# Schematic.net
KiCad netlist of a schematic drawn in Altium Designer
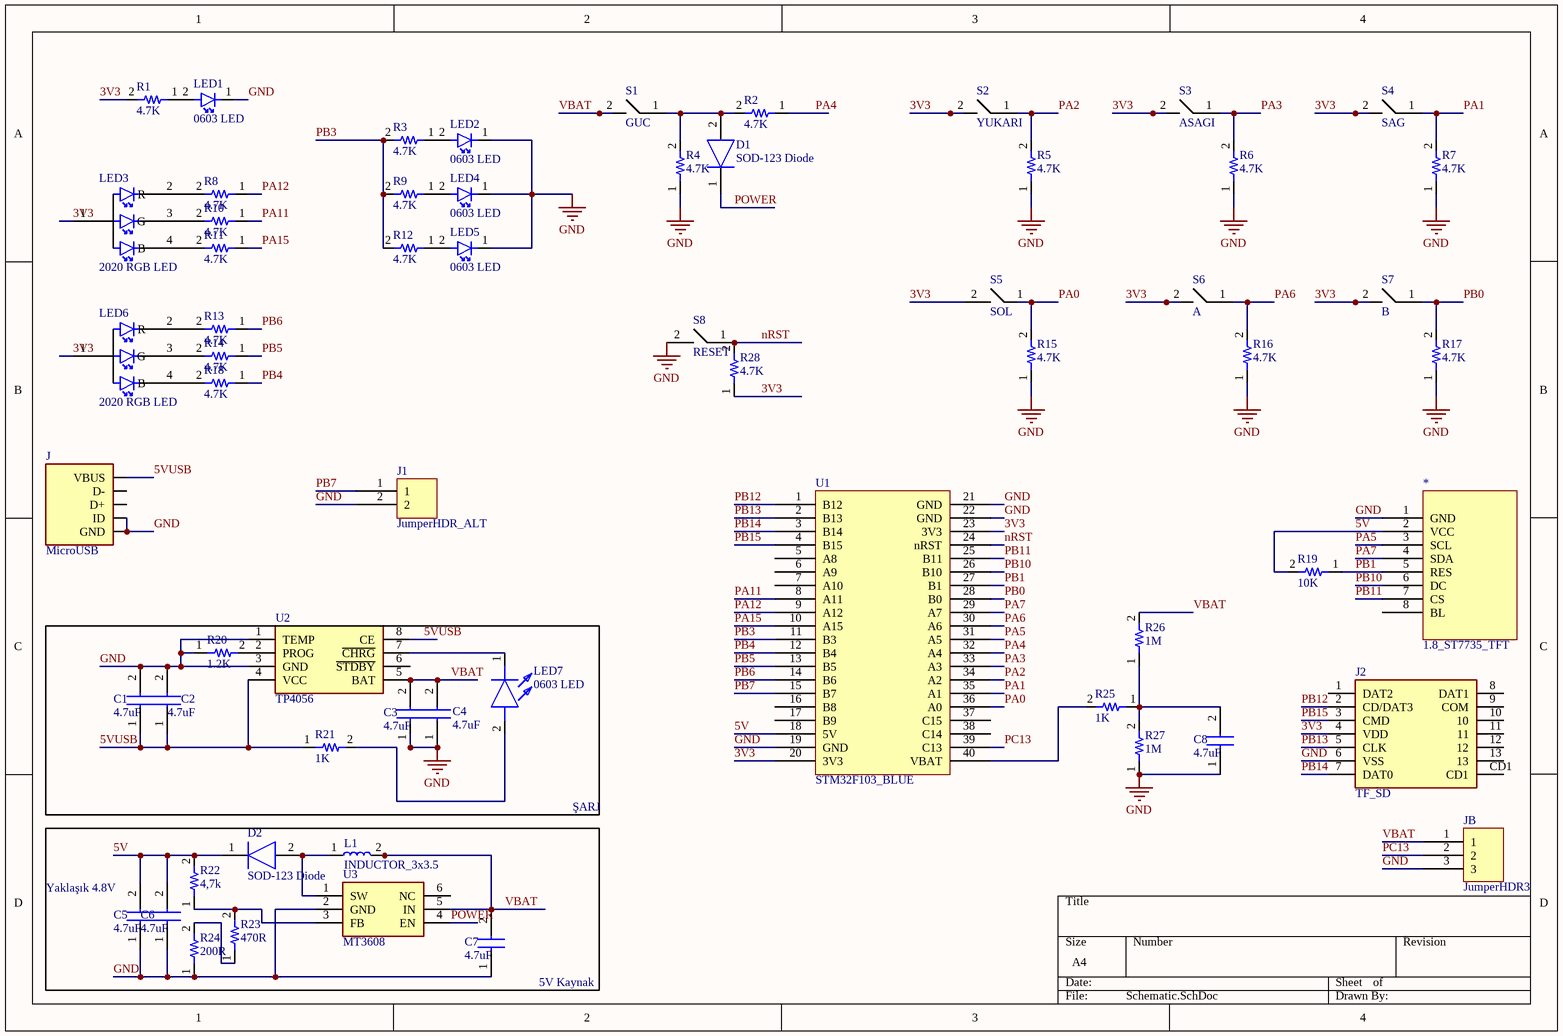
[diagram p0: Schematic.SchDoc]

(export (version "E")
  (design (tool "Eeschema 10.0.6"))
  (components
    (comp (ref "*")
      (value "1.8_ST7735_TFT")
      (footprint "1.8_ST7735_TFT")
      (libsource (lib "uAltiumLib") (part "1.8_ST7735_TFT"))
    )
    (comp (ref "C1")
      (value "4.7uF")
      (footprint "0603 Capacitor")
      (description "Capacitor")
      (fields
        (field (name "MANUFACTURER_PART_NUMBER") "06031A120JAT2A")
        (field (name "MOUSER PART NUMBER") "581-06031A120J")
      )
      (libsource (lib "uAltiumLib") (part "0603 Capacitor"))
    )
    (comp (ref "C2")
      (value "4.7uF")
      (footprint "0603 Capacitor")
      (description "Capacitor")
      (fields
        (field (name "MANUFACTURER_PART_NUMBER") "06031A120JAT2A")
        (field (name "MOUSER PART NUMBER") "581-06031A120J")
      )
      (libsource (lib "uAltiumLib") (part "0603 Capacitor"))
    )
    (comp (ref "C3")
      (value "4.7uF")
      (footprint "0603 Capacitor")
      (description "Capacitor")
      (fields
        (field (name "MANUFACTURER_PART_NUMBER") "06031A120JAT2A")
        (field (name "MOUSER PART NUMBER") "581-06031A120J")
      )
      (libsource (lib "uAltiumLib") (part "0603 Capacitor"))
    )
    (comp (ref "C4")
      (value "4.7uF")
      (footprint "0603 Capacitor")
      (description "Capacitor")
      (fields
        (field (name "MANUFACTURER_PART_NUMBER") "06031A120JAT2A")
        (field (name "MOUSER PART NUMBER") "581-06031A120J")
      )
      (libsource (lib "uAltiumLib") (part "0603 Capacitor"))
    )
    (comp (ref "C5")
      (value "4.7uF")
      (footprint "0603 Capacitor")
      (description "Capacitor")
      (fields
        (field (name "MANUFACTURER_PART_NUMBER") "06031A120JAT2A")
        (field (name "MOUSER PART NUMBER") "581-06031A120J")
      )
      (libsource (lib "uAltiumLib") (part "0603 Capacitor"))
    )
    (comp (ref "C6")
      (value "4.7uF")
      (footprint "0603 Capacitor")
      (description "Capacitor")
      (fields
        (field (name "MANUFACTURER_PART_NUMBER") "06031A120JAT2A")
        (field (name "MOUSER PART NUMBER") "581-06031A120J")
      )
      (libsource (lib "uAltiumLib") (part "0603 Capacitor"))
    )
    (comp (ref "C7")
      (value "4.7uF")
      (footprint "0603 Capacitor")
      (description "Capacitor")
      (fields
        (field (name "MANUFACTURER_PART_NUMBER") "06031A120JAT2A")
        (field (name "MOUSER PART NUMBER") "581-06031A120J")
      )
      (libsource (lib "uAltiumLib") (part "0603 Capacitor"))
    )
    (comp (ref "C8")
      (value "4.7uF")
      (footprint "0603 Capacitor")
      (description "Capacitor")
      (fields
        (field (name "MANUFACTURER_PART_NUMBER") "06031A120JAT2A")
        (field (name "MOUSER PART NUMBER") "581-06031A120J")
      )
      (libsource (lib "uAltiumLib") (part "0603 Capacitor"))
    )
    (comp (ref "D1")
      (value "SOD-123 Diode")
      (footprint "SOD123")
      (description "Diode")
      (fields
        (field (name "MANUFACTURER_PART_NUMBER") "1N4148W-G3-08")
        (field (name "MOUSER PART NUMBER") "78-1N4148W-G3-08")
      )
      (libsource (lib "uAltiumLib") (part "SOD-123 Diode"))
    )
    (comp (ref "D2")
      (value "SOD-123 Diode")
      (footprint "SOD123")
      (description "Diode")
      (fields
        (field (name "MANUFACTURER_PART_NUMBER") "1N4148W-G3-08")
        (field (name "MOUSER PART NUMBER") "78-1N4148W-G3-08")
      )
      (libsource (lib "uAltiumLib") (part "SOD-123 Diode"))
    )
    (comp (ref "J")
      (value "MicroUSB")
      (footprint "MicroUSB")
      (fields (field (name "MP") "ZX62-B-5PA") (field (name "MF") "Hirose"))
      (libsource (lib "uAltiumLib") (part "MicroUSB"))
    )
    (comp (ref "J1")
      (value "JumperHDR_ALT")
      (footprint "JumperHDR")
      (libsource (lib "uAltiumLib") (part "JumperHDR_ALT"))
    )
    (comp (ref "J2")
      (value "TF_SD")
      (footprint "TF_SD")
      (description "Connector")
      (fields
        (field (name "MANUFACTURER_PART_NUMBER") "045138008100858+")
        (field (name "MOUSER PART NUMBER") "581-045138008100858+")
      )
      (libsource (lib "uAltiumLib") (part "TF_SD"))
    )
    (comp (ref "JB")
      (value "JumperHDR3")
      (footprint "JumperHDR3")
      (libsource (lib "uAltiumLib") (part "JumperHDR3"))
    )
    (comp (ref "L1")
      (value "INDUCTOR_3x3.5")
      (footprint "INDUCTOR_3x3.5")
      (description "Inductor")
      (fields (field (name "MANUFACTURER_PART_NUMBER") "CD32-4R7M"))
      (libsource (lib "uAltiumLib") (part "INDUCTOR_3x3.5"))
    )
    (comp (ref "LED1")
      (value "0603 LED")
      (footprint "0603 LED")
      (description "LED")
      (fields
        (field (name "MANUFACTURER_PART_NUMBER") "150060GS55040")
        (field (name "MOUSER PART NUMBER") "710-150060GS55040")
      )
      (libsource (lib "") (part "0603 LED_1"))
    )
    (comp (ref "LED2")
      (value "0603 LED")
      (footprint "0603 LED")
      (description "LED")
      (fields
        (field (name "MANUFACTURER_PART_NUMBER") "150060GS55040")
        (field (name "MOUSER PART NUMBER") "710-150060GS55040")
      )
      (libsource (lib "") (part "0603 LED_1"))
    )
    (comp (ref "LED3")
      (value "2020 RGB LED")
      (footprint "20x20 RGB LED")
      (description "LED")
      (fields (field (name "MANUFACTURER_PART_NUMBER") "FM-B2020RGBA-HG"))
      (libsource (lib "uAltiumLib") (part "2020 RGB LED"))
    )
    (comp (ref "LED4")
      (value "0603 LED")
      (footprint "0603 LED")
      (description "LED")
      (fields
        (field (name "MANUFACTURER_PART_NUMBER") "150060GS55040")
        (field (name "MOUSER PART NUMBER") "710-150060GS55040")
      )
      (libsource (lib "") (part "0603 LED_1"))
    )
    (comp (ref "LED5")
      (value "0603 LED")
      (footprint "0603 LED")
      (description "LED")
      (fields
        (field (name "MANUFACTURER_PART_NUMBER") "150060GS55040")
        (field (name "MOUSER PART NUMBER") "710-150060GS55040")
      )
      (libsource (lib "") (part "0603 LED_1"))
    )
    (comp (ref "LED6")
      (value "2020 RGB LED")
      (footprint "20x20 RGB LED")
      (description "LED")
      (fields (field (name "MANUFACTURER_PART_NUMBER") "FM-B2020RGBA-HG"))
      (libsource (lib "uAltiumLib") (part "2020 RGB LED"))
    )
    (comp (ref "LED7")
      (value "0603 LED")
      (footprint "0603 LED")
      (description "LED")
      (fields
        (field (name "MANUFACTURER_PART_NUMBER") "150060GS55040")
        (field (name "MOUSER PART NUMBER") "710-150060GS55040")
      )
      (libsource (lib "uAltiumLib") (part "0603 LED"))
    )
    (comp (ref "R1")
      (value "4.7K")
      (footprint "0603 Resistor")
      (description "Resistor")
      (fields
        (field (name "MANUFACTURER_PART_NUMBER") "CPF0603B100RE1")
        (field (name "MOUSER PART NUMBER") "279-CPF0603B100RE1")
      )
      (libsource (lib "uAltiumLib") (part "0603 Resistor"))
    )
    (comp (ref "R2")
      (value "4.7K")
      (footprint "0603 Resistor")
      (description "Resistor")
      (fields
        (field (name "MANUFACTURER_PART_NUMBER") "CPF0603B100RE1")
        (field (name "MOUSER PART NUMBER") "279-CPF0603B100RE1")
      )
      (libsource (lib "uAltiumLib") (part "0603 Resistor"))
    )
    (comp (ref "R3")
      (value "4.7K")
      (footprint "0603 Resistor")
      (description "Resistor")
      (fields
        (field (name "MANUFACTURER_PART_NUMBER") "CPF0603B100RE1")
        (field (name "MOUSER PART NUMBER") "279-CPF0603B100RE1")
      )
      (libsource (lib "uAltiumLib") (part "0603 Resistor"))
    )
    (comp (ref "R4")
      (value "4.7K")
      (footprint "0603 Resistor")
      (description "Resistor")
      (fields
        (field (name "MANUFACTURER_PART_NUMBER") "CPF0603B100RE1")
        (field (name "MOUSER PART NUMBER") "279-CPF0603B100RE1")
      )
      (libsource (lib "uAltiumLib") (part "0603 Resistor"))
    )
    (comp (ref "R5")
      (value "4.7K")
      (footprint "0603 Resistor")
      (description "Resistor")
      (fields
        (field (name "MANUFACTURER_PART_NUMBER") "CPF0603B100RE1")
        (field (name "MOUSER PART NUMBER") "279-CPF0603B100RE1")
      )
      (libsource (lib "uAltiumLib") (part "0603 Resistor"))
    )
    (comp (ref "R6")
      (value "4.7K")
      (footprint "0603 Resistor")
      (description "Resistor")
      (fields
        (field (name "MANUFACTURER_PART_NUMBER") "CPF0603B100RE1")
        (field (name "MOUSER PART NUMBER") "279-CPF0603B100RE1")
      )
      (libsource (lib "uAltiumLib") (part "0603 Resistor"))
    )
    (comp (ref "R7")
      (value "4.7K")
      (footprint "0603 Resistor")
      (description "Resistor")
      (fields
        (field (name "MANUFACTURER_PART_NUMBER") "CPF0603B100RE1")
        (field (name "MOUSER PART NUMBER") "279-CPF0603B100RE1")
      )
      (libsource (lib "uAltiumLib") (part "0603 Resistor"))
    )
    (comp (ref "R8")
      (value "4.7K")
      (footprint "0603 Resistor")
      (description "Resistor")
      (fields
        (field (name "MANUFACTURER_PART_NUMBER") "CPF0603B100RE1")
        (field (name "MOUSER PART NUMBER") "279-CPF0603B100RE1")
      )
      (libsource (lib "uAltiumLib") (part "0603 Resistor"))
    )
    (comp (ref "R9")
      (value "4.7K")
      (footprint "0603 Resistor")
      (description "Resistor")
      (fields
        (field (name "MANUFACTURER_PART_NUMBER") "CPF0603B100RE1")
        (field (name "MOUSER PART NUMBER") "279-CPF0603B100RE1")
      )
      (libsource (lib "uAltiumLib") (part "0603 Resistor"))
    )
    (comp (ref "R10")
      (value "4.7K")
      (footprint "0603 Resistor")
      (description "Resistor")
      (fields
        (field (name "MANUFACTURER_PART_NUMBER") "CPF0603B100RE1")
        (field (name "MOUSER PART NUMBER") "279-CPF0603B100RE1")
      )
      (libsource (lib "uAltiumLib") (part "0603 Resistor"))
    )
    (comp (ref "R11")
      (value "4.7K")
      (footprint "0603 Resistor")
      (description "Resistor")
      (fields
        (field (name "MANUFACTURER_PART_NUMBER") "CPF0603B100RE1")
        (field (name "MOUSER PART NUMBER") "279-CPF0603B100RE1")
      )
      (libsource (lib "uAltiumLib") (part "0603 Resistor"))
    )
    (comp (ref "R12")
      (value "4.7K")
      (footprint "0603 Resistor")
      (description "Resistor")
      (fields
        (field (name "MANUFACTURER_PART_NUMBER") "CPF0603B100RE1")
        (field (name "MOUSER PART NUMBER") "279-CPF0603B100RE1")
      )
      (libsource (lib "uAltiumLib") (part "0603 Resistor"))
    )
    (comp (ref "R13")
      (value "4.7K")
      (footprint "0603 Resistor")
      (description "Resistor")
      (fields
        (field (name "MANUFACTURER_PART_NUMBER") "CPF0603B100RE1")
        (field (name "MOUSER PART NUMBER") "279-CPF0603B100RE1")
      )
      (libsource (lib "uAltiumLib") (part "0603 Resistor"))
    )
    (comp (ref "R14")
      (value "4.7K")
      (footprint "0603 Resistor")
      (description "Resistor")
      (fields
        (field (name "MANUFACTURER_PART_NUMBER") "CPF0603B100RE1")
        (field (name "MOUSER PART NUMBER") "279-CPF0603B100RE1")
      )
      (libsource (lib "uAltiumLib") (part "0603 Resistor"))
    )
    (comp (ref "R15")
      (value "4.7K")
      (footprint "0603 Resistor")
      (description "Resistor")
      (fields
        (field (name "MANUFACTURER_PART_NUMBER") "CPF0603B100RE1")
        (field (name "MOUSER PART NUMBER") "279-CPF0603B100RE1")
      )
      (libsource (lib "uAltiumLib") (part "0603 Resistor"))
    )
    (comp (ref "R16")
      (value "4.7K")
      (footprint "0603 Resistor")
      (description "Resistor")
      (fields
        (field (name "MANUFACTURER_PART_NUMBER") "CPF0603B100RE1")
        (field (name "MOUSER PART NUMBER") "279-CPF0603B100RE1")
      )
      (libsource (lib "uAltiumLib") (part "0603 Resistor"))
    )
    (comp (ref "R17")
      (value "4.7K")
      (footprint "0603 Resistor")
      (description "Resistor")
      (fields
        (field (name "MANUFACTURER_PART_NUMBER") "CPF0603B100RE1")
        (field (name "MOUSER PART NUMBER") "279-CPF0603B100RE1")
      )
      (libsource (lib "uAltiumLib") (part "0603 Resistor"))
    )
    (comp (ref "R18")
      (value "4.7K")
      (footprint "0603 Resistor")
      (description "Resistor")
      (fields
        (field (name "MANUFACTURER_PART_NUMBER") "CPF0603B100RE1")
        (field (name "MOUSER PART NUMBER") "279-CPF0603B100RE1")
      )
      (libsource (lib "uAltiumLib") (part "0603 Resistor"))
    )
    (comp (ref "R19")
      (value "10K")
      (footprint "0603 Resistor")
      (description "Resistor")
      (fields
        (field (name "MANUFACTURER_PART_NUMBER") "CPF0603B100RE1")
        (field (name "MOUSER PART NUMBER") "279-CPF0603B100RE1")
      )
      (libsource (lib "uAltiumLib") (part "0603 Resistor"))
    )
    (comp (ref "R20")
      (value "1.2K")
      (footprint "0603 Resistor")
      (description "Resistor")
      (fields
        (field (name "MANUFACTURER_PART_NUMBER") "CPF0603B100RE1")
        (field (name "MOUSER PART NUMBER") "279-CPF0603B100RE1")
      )
      (libsource (lib "uAltiumLib") (part "0603 Resistor"))
    )
    (comp (ref "R21")
      (value "1K")
      (footprint "0603 Resistor")
      (description "Resistor")
      (fields
        (field (name "MANUFACTURER_PART_NUMBER") "CPF0603B100RE1")
        (field (name "MOUSER PART NUMBER") "279-CPF0603B100RE1")
      )
      (libsource (lib "uAltiumLib") (part "0603 Resistor"))
    )
    (comp (ref "R22")
      (value "4,7k")
      (footprint "0603 Resistor")
      (description "Resistor")
      (fields
        (field (name "MANUFACTURER_PART_NUMBER") "CPF0603B100RE1")
        (field (name "MOUSER PART NUMBER") "279-CPF0603B100RE1")
      )
      (libsource (lib "uAltiumLib") (part "0603 Resistor"))
    )
    (comp (ref "R23")
      (value "470R")
      (footprint "0603 Resistor")
      (description "Resistor")
      (fields
        (field (name "MANUFACTURER_PART_NUMBER") "CPF0603B100RE1")
        (field (name "MOUSER PART NUMBER") "279-CPF0603B100RE1")
      )
      (libsource (lib "uAltiumLib") (part "0603 Resistor"))
    )
    (comp (ref "R24")
      (value "200R")
      (footprint "0603 Resistor")
      (description "Resistor")
      (fields
        (field (name "MANUFACTURER_PART_NUMBER") "CPF0603B100RE1")
        (field (name "MOUSER PART NUMBER") "279-CPF0603B100RE1")
      )
      (libsource (lib "uAltiumLib") (part "0603 Resistor"))
    )
    (comp (ref "R25")
      (value "1K")
      (footprint "0603 Resistor")
      (description "Resistor")
      (fields
        (field (name "MANUFACTURER_PART_NUMBER") "CPF0603B100RE1")
        (field (name "MOUSER PART NUMBER") "279-CPF0603B100RE1")
      )
      (libsource (lib "uAltiumLib") (part "0603 Resistor"))
    )
    (comp (ref "R26")
      (value "1M")
      (footprint "0603 Resistor")
      (description "Resistor")
      (fields
        (field (name "MANUFACTURER_PART_NUMBER") "CPF0603B100RE1")
        (field (name "MOUSER PART NUMBER") "279-CPF0603B100RE1")
      )
      (libsource (lib "uAltiumLib") (part "0603 Resistor"))
    )
    (comp (ref "R27")
      (value "1M")
      (footprint "0603 Resistor")
      (description "Resistor")
      (fields
        (field (name "MANUFACTURER_PART_NUMBER") "CPF0603B100RE1")
        (field (name "MOUSER PART NUMBER") "279-CPF0603B100RE1")
      )
      (libsource (lib "uAltiumLib") (part "0603 Resistor"))
    )
    (comp (ref "R28")
      (value "4.7K")
      (footprint "0603 Resistor")
      (description "Resistor")
      (fields
        (field (name "MANUFACTURER_PART_NUMBER") "CPF0603B100RE1")
        (field (name "MOUSER PART NUMBER") "279-CPF0603B100RE1")
      )
      (libsource (lib "uAltiumLib") (part "0603 Resistor"))
    )
    (comp (ref "S1")
      (value "GUC")
      (footprint "TACT SWITCH SMD")
      (fields (field (name "MP") "B3F-1000") (field (name "MF") "Omron"))
      (libsource (lib "uAltiumLib") (part "TACT SWITCH SMD"))
    )
    (comp (ref "S2")
      (value "YUKARI")
      (footprint "12x12 Tact Switch")
      (description "Switch")
      (fields
        (field (name "MANUFACTURER_PART_NUMBER") "B3F-4005")
        (field (name "MOUSER PART NUMBER") "653-B3F-4005")
      )
      (libsource (lib "uAltiumLib") (part "TACTSWITCH_12x12"))
    )
    (comp (ref "S3")
      (value "ASAGI")
      (footprint "12x12 Tact Switch")
      (description "Switch")
      (fields
        (field (name "MANUFACTURER_PART_NUMBER") "B3F-4005")
        (field (name "MOUSER PART NUMBER") "653-B3F-4005")
      )
      (libsource (lib "uAltiumLib") (part "TACTSWITCH_12x12"))
    )
    (comp (ref "S4")
      (value "SAG")
      (footprint "12x12 Tact Switch")
      (description "Switch")
      (fields
        (field (name "MANUFACTURER_PART_NUMBER") "B3F-4005")
        (field (name "MOUSER PART NUMBER") "653-B3F-4005")
      )
      (libsource (lib "uAltiumLib") (part "TACTSWITCH_12x12"))
    )
    (comp (ref "S5")
      (value "SOL")
      (footprint "12x12 Tact Switch")
      (description "Switch")
      (fields
        (field (name "MANUFACTURER_PART_NUMBER") "B3F-4005")
        (field (name "MOUSER PART NUMBER") "653-B3F-4005")
      )
      (libsource (lib "uAltiumLib") (part "TACTSWITCH_12x12"))
    )
    (comp (ref "S6")
      (value "A")
      (footprint "12x12 Tact Switch")
      (description "Switch")
      (fields
        (field (name "MANUFACTURER_PART_NUMBER") "B3F-4005")
        (field (name "MOUSER PART NUMBER") "653-B3F-4005")
      )
      (libsource (lib "uAltiumLib") (part "TACTSWITCH_12x12"))
    )
    (comp (ref "S7")
      (value "B")
      (footprint "12x12 Tact Switch")
      (description "Switch")
      (fields
        (field (name "MANUFACTURER_PART_NUMBER") "B3F-4005")
        (field (name "MOUSER PART NUMBER") "653-B3F-4005")
      )
      (libsource (lib "uAltiumLib") (part "TACTSWITCH_12x12"))
    )
    (comp (ref "S8")
      (value "RESET")
      (footprint "TACT SWITCH SMD")
      (fields (field (name "MP") "B3F-1000") (field (name "MF") "Omron"))
      (libsource (lib "uAltiumLib") (part "TACT SWITCH SMD"))
    )
    (comp (ref "U1")
      (value "STM32F103_BLUE")
      (footprint "STM32_BLUE_PILL")
      (libsource (lib "uAltiumLib") (part "STM32F103_BLUE"))
    )
    (comp (ref "U2")
      (value "TP4056")
      (footprint "TP4056A")
      (description "Connector")
      (libsource (lib "uAltiumLib") (part "TP4056"))
    )
    (comp (ref "U3")
      (value "MT3608")
      (footprint "MT3608")
      (description "Undefined or Miscellaneous")
      (libsource (lib "uAltiumLib") (part "MT3608"))
    )
  )
  (nets
    (net (code "1") (name "/3V3") (class "Default")
      (node (ref "J2") (pin "4") (pinfunction "VDD_4") (pintype "passive"))
      (node (ref "LED3") (pin "1") (pintype "passive"))
      (node (ref "LED6") (pin "1") (pintype "passive"))
      (node (ref "R1") (pin "2") (pinfunction "2_2") (pintype "passive"))
      (node (ref "R28") (pin "1") (pinfunction "1_1") (pintype "passive"))
      (node (ref "S2") (pin "2") (pintype "passive"))
      (node (ref "S3") (pin "2") (pintype "passive"))
      (node (ref "S4") (pin "2") (pintype "passive"))
      (node (ref "S5") (pin "2") (pintype "passive"))
      (node (ref "S6") (pin "2") (pintype "passive"))
      (node (ref "S7") (pin "2") (pintype "passive"))
      (node (ref "U1") (pin "20") (pinfunction "3V3_20") (pintype "passive"))
      (node (ref "U1") (pin "23") (pinfunction "3V3_23") (pintype "passive"))
    )
    (net (code "2") (name "/5V") (class "Default")
      (node (ref "*") (pin "2") (pinfunction "VCC_2") (pintype "passive"))
      (node (ref "C5") (pin "2") (pinfunction "2_2") (pintype "passive"))
      (node (ref "C6") (pin "2") (pinfunction "2_2") (pintype "passive"))
      (node (ref "D2") (pin "1") (pinfunction "K_1") (pintype "passive"))
      (node (ref "R19") (pin "2") (pinfunction "2_2") (pintype "passive"))
      (node (ref "R22") (pin "2") (pinfunction "2_2") (pintype "passive"))
      (node (ref "U1") (pin "18") (pinfunction "5V_18") (pintype "passive"))
    )
    (net (code "3") (name "/5VUSB") (class "Default")
      (node (ref "C1") (pin "1") (pinfunction "1_1") (pintype "passive"))
      (node (ref "C2") (pin "1") (pinfunction "1_1") (pintype "passive"))
      (node (ref "J") (pin "1") (pinfunction "VBUS_1") (pintype "power_in"))
      (node (ref "R21") (pin "1") (pinfunction "1_1") (pintype "passive"))
      (node (ref "U2") (pin "4") (pinfunction "VCC_4") (pintype "passive"))
      (node (ref "U2") (pin "8") (pinfunction "CE_8") (pintype "passive"))
    )
    (net (code "4") (name "/PA0") (class "Default")
      (node (ref "R15") (pin "2") (pinfunction "2_2") (pintype "passive"))
      (node (ref "S5") (pin "1") (pintype "passive"))
      (node (ref "U1") (pin "36") (pinfunction "A0_36") (pintype "passive"))
    )
    (net (code "5") (name "/PA1") (class "Default")
      (node (ref "R7") (pin "2") (pinfunction "2_2") (pintype "passive"))
      (node (ref "S4") (pin "1") (pintype "passive"))
      (node (ref "U1") (pin "35") (pinfunction "A1_35") (pintype "passive"))
    )
    (net (code "6") (name "/PA2") (class "Default")
      (node (ref "R5") (pin "2") (pinfunction "2_2") (pintype "passive"))
      (node (ref "S2") (pin "1") (pintype "passive"))
      (node (ref "U1") (pin "34") (pinfunction "A2_34") (pintype "passive"))
    )
    (net (code "7") (name "/PA3") (class "Default")
      (node (ref "R6") (pin "2") (pinfunction "2_2") (pintype "passive"))
      (node (ref "S3") (pin "1") (pintype "passive"))
      (node (ref "U1") (pin "33") (pinfunction "A3_33") (pintype "passive"))
    )
    (net (code "8") (name "/PA4") (class "Default")
      (node (ref "R2") (pin "1") (pinfunction "1_1") (pintype "passive"))
      (node (ref "U1") (pin "32") (pinfunction "A4_32") (pintype "passive"))
    )
    (net (code "9") (name "/PA5") (class "Default")
      (node (ref "*") (pin "3") (pinfunction "SCL_3") (pintype "passive"))
      (node (ref "U1") (pin "31") (pinfunction "A5_31") (pintype "passive"))
    )
    (net (code "10") (name "/PA6") (class "Default")
      (node (ref "R16") (pin "2") (pinfunction "2_2") (pintype "passive"))
      (node (ref "S6") (pin "1") (pintype "passive"))
      (node (ref "U1") (pin "30") (pinfunction "A6_30") (pintype "passive"))
    )
    (net (code "11") (name "/PA7") (class "Default")
      (node (ref "*") (pin "4") (pinfunction "SDA_4") (pintype "passive"))
      (node (ref "U1") (pin "29") (pinfunction "A7_29") (pintype "passive"))
    )
    (net (code "12") (name "/PA11") (class "Default")
      (node (ref "R10") (pin "1") (pinfunction "1_1") (pintype "passive"))
      (node (ref "U1") (pin "8") (pinfunction "A11_8") (pintype "passive"))
    )
    (net (code "13") (name "/PA12") (class "Default")
      (node (ref "R8") (pin "1") (pinfunction "1_1") (pintype "passive"))
      (node (ref "U1") (pin "9") (pinfunction "A12_9") (pintype "passive"))
    )
    (net (code "14") (name "/PA15") (class "Default")
      (node (ref "R11") (pin "1") (pinfunction "1_1") (pintype "passive"))
      (node (ref "U1") (pin "10") (pinfunction "A15_10") (pintype "passive"))
    )
    (net (code "15") (name "/PB0") (class "Default")
      (node (ref "R17") (pin "2") (pinfunction "2_2") (pintype "passive"))
      (node (ref "S7") (pin "1") (pintype "passive"))
      (node (ref "U1") (pin "28") (pinfunction "B0_28") (pintype "passive"))
    )
    (net (code "16") (name "/PB1") (class "Default")
      (node (ref "*") (pin "5") (pinfunction "RES_5") (pintype "passive"))
      (node (ref "R19") (pin "1") (pinfunction "1_1") (pintype "passive"))
      (node (ref "U1") (pin "27") (pinfunction "B1_27") (pintype "passive"))
    )
    (net (code "17") (name "/PB3") (class "Default")
      (node (ref "R12") (pin "2") (pinfunction "2_2") (pintype "passive"))
      (node (ref "R3") (pin "2") (pinfunction "2_2") (pintype "passive"))
      (node (ref "R9") (pin "2") (pinfunction "2_2") (pintype "passive"))
      (node (ref "U1") (pin "11") (pinfunction "B3_11") (pintype "passive"))
    )
    (net (code "18") (name "/PB4") (class "Default")
      (node (ref "R18") (pin "1") (pinfunction "1_1") (pintype "passive"))
      (node (ref "U1") (pin "12") (pinfunction "B4_12") (pintype "passive"))
    )
    (net (code "19") (name "/PB5") (class "Default")
      (node (ref "R14") (pin "1") (pinfunction "1_1") (pintype "passive"))
      (node (ref "U1") (pin "13") (pinfunction "B5_13") (pintype "passive"))
    )
    (net (code "20") (name "/PB6") (class "Default")
      (node (ref "R13") (pin "1") (pinfunction "1_1") (pintype "passive"))
      (node (ref "U1") (pin "14") (pinfunction "B6_14") (pintype "passive"))
    )
    (net (code "21") (name "/PB7") (class "Default")
      (node (ref "J1") (pin "1") (pinfunction "1_1") (pintype "passive"))
      (node (ref "U1") (pin "15") (pinfunction "B7_15") (pintype "passive"))
    )
    (net (code "22") (name "/PB10") (class "Default")
      (node (ref "*") (pin "6") (pinfunction "DC_6") (pintype "passive"))
      (node (ref "U1") (pin "26") (pinfunction "B10_26") (pintype "passive"))
    )
    (net (code "23") (name "/PB11") (class "Default")
      (node (ref "*") (pin "7") (pinfunction "CS_7") (pintype "passive"))
      (node (ref "U1") (pin "25") (pinfunction "B11_25") (pintype "passive"))
    )
    (net (code "24") (name "/PB12") (class "Default")
      (node (ref "J2") (pin "2") (pinfunction "CD/DAT3_2") (pintype "passive"))
      (node (ref "U1") (pin "1") (pinfunction "B12_1") (pintype "passive"))
    )
    (net (code "25") (name "/PB13") (class "Default")
      (node (ref "J2") (pin "5") (pinfunction "CLK_5") (pintype "passive"))
      (node (ref "U1") (pin "2") (pinfunction "B13_2") (pintype "passive"))
    )
    (net (code "26") (name "/PB14") (class "Default")
      (node (ref "J2") (pin "7") (pinfunction "DAT0_7") (pintype "passive"))
      (node (ref "U1") (pin "3") (pinfunction "B14_3") (pintype "passive"))
    )
    (net (code "27") (name "/PB15") (class "Default")
      (node (ref "J2") (pin "3") (pinfunction "CMD_3") (pintype "passive"))
      (node (ref "U1") (pin "4") (pinfunction "B15_4") (pintype "passive"))
    )
    (net (code "28") (name "/PC13") (class "Default")
      (node (ref "JB") (pin "2") (pinfunction "2_2") (pintype "passive"))
      (node (ref "U1") (pin "39") (pinfunction "C13_39") (pintype "passive"))
    )
    (net (code "29") (name "/POWER") (class "Default")
      (node (ref "D1") (pin "1") (pinfunction "K_1") (pintype "passive"))
      (node (ref "U3") (pin "4") (pinfunction "EN_4") (pintype "passive"))
    )
    (net (code "30") (name "/VBAT") (class "Default")
      (node (ref "C3") (pin "2") (pinfunction "2_2") (pintype "passive"))
      (node (ref "C4") (pin "2") (pinfunction "2_2") (pintype "passive"))
      (node (ref "C7") (pin "2") (pinfunction "2_2") (pintype "passive"))
      (node (ref "JB") (pin "1") (pinfunction "1_1") (pintype "passive"))
      (node (ref "L1") (pin "2") (pinfunction "2_2") (pintype "passive"))
      (node (ref "R26") (pin "2") (pinfunction "2_2") (pintype "passive"))
      (node (ref "S1") (pin "2") (pintype "passive"))
      (node (ref "U2") (pin "5") (pinfunction "BAT_5") (pintype "passive"))
      (node (ref "U3") (pin "5") (pinfunction "IN_5") (pintype "passive"))
    )
    (net (code "31") (name "/nRST") (class "Default")
      (node (ref "R28") (pin "2") (pinfunction "2_2") (pintype "passive"))
      (node (ref "S8") (pin "1") (pintype "passive"))
      (node (ref "U1") (pin "24") (pinfunction "nRST_24") (pintype "passive"))
    )
    (net (code "32") (name "GND") (class "Default")
      (node (ref "*") (pin "1") (pinfunction "GND_1") (pintype "passive"))
      (node (ref "C1") (pin "2") (pinfunction "2_2") (pintype "passive"))
      (node (ref "C2") (pin "2") (pinfunction "2_2") (pintype "passive"))
      (node (ref "C3") (pin "1") (pinfunction "1_1") (pintype "passive"))
      (node (ref "C4") (pin "1") (pinfunction "1_1") (pintype "passive"))
      (node (ref "C5") (pin "1") (pinfunction "1_1") (pintype "passive"))
      (node (ref "C6") (pin "1") (pinfunction "1_1") (pintype "passive"))
      (node (ref "C7") (pin "1") (pinfunction "1_1") (pintype "passive"))
      (node (ref "C8") (pin "1") (pinfunction "1_1") (pintype "passive"))
      (node (ref "J") (pin "4") (pinfunction "ID_4") (pintype "passive"))
      (node (ref "J") (pin "5") (pinfunction "GND_5") (pintype "power_in"))
      (node (ref "J1") (pin "2") (pinfunction "2_2") (pintype "passive"))
      (node (ref "J2") (pin "6") (pinfunction "VSS_6") (pintype "passive"))
      (node (ref "JB") (pin "3") (pinfunction "3_3") (pintype "passive"))
      (node (ref "LED1") (pin "1") (pinfunction "K_1") (pintype "passive"))
      (node (ref "LED2") (pin "1") (pinfunction "K_1") (pintype "passive"))
      (node (ref "LED4") (pin "1") (pinfunction "K_1") (pintype "passive"))
      (node (ref "LED5") (pin "1") (pinfunction "K_1") (pintype "passive"))
      (node (ref "R15") (pin "1") (pinfunction "1_1") (pintype "passive"))
      (node (ref "R16") (pin "1") (pinfunction "1_1") (pintype "passive"))
      (node (ref "R17") (pin "1") (pinfunction "1_1") (pintype "passive"))
      (node (ref "R20") (pin "1") (pinfunction "1_1") (pintype "passive"))
      (node (ref "R24") (pin "1") (pinfunction "1_1") (pintype "passive"))
      (node (ref "R27") (pin "1") (pinfunction "1_1") (pintype "passive"))
      (node (ref "R4") (pin "1") (pinfunction "1_1") (pintype "passive"))
      (node (ref "R5") (pin "1") (pinfunction "1_1") (pintype "passive"))
      (node (ref "R6") (pin "1") (pinfunction "1_1") (pintype "passive"))
      (node (ref "R7") (pin "1") (pinfunction "1_1") (pintype "passive"))
      (node (ref "S8") (pin "2") (pintype "passive"))
      (node (ref "U1") (pin "19") (pinfunction "GND_19") (pintype "passive"))
      (node (ref "U1") (pin "21") (pinfunction "GND_21") (pintype "passive"))
      (node (ref "U1") (pin "22") (pinfunction "GND_22") (pintype "passive"))
      (node (ref "U2") (pin "1") (pinfunction "TEMP_1") (pintype "passive"))
      (node (ref "U2") (pin "3") (pinfunction "GND_3") (pintype "passive"))
      (node (ref "U3") (pin "2") (pinfunction "GND_2") (pintype "passive"))
    )
    (net (code "33") (name "Net-(C8-Pad2)") (class "Default")
      (node (ref "C8") (pin "2") (pinfunction "2_2") (pintype "passive"))
      (node (ref "R25") (pin "1") (pinfunction "1_1") (pintype "passive"))
      (node (ref "R26") (pin "1") (pinfunction "1_1") (pintype "passive"))
      (node (ref "R27") (pin "2") (pinfunction "2_2") (pintype "passive"))
    )
    (net (code "34") (name "Net-(D1-A)") (class "Default")
      (node (ref "D1") (pin "2") (pinfunction "A_2") (pintype "passive"))
      (node (ref "R2") (pin "2") (pinfunction "2_2") (pintype "passive"))
      (node (ref "R4") (pin "2") (pinfunction "2_2") (pintype "passive"))
      (node (ref "S1") (pin "1") (pintype "passive"))
    )
    (net (code "35") (name "Net-(D2-A)") (class "Default")
      (node (ref "D2") (pin "2") (pinfunction "A_2") (pintype "passive"))
      (node (ref "L1") (pin "1") (pinfunction "1_1") (pintype "passive"))
      (node (ref "U3") (pin "1") (pinfunction "SW_1") (pintype "passive"))
    )
    (net (code "36") (name "Net-(LED1-A)") (class "Default")
      (node (ref "LED1") (pin "2") (pinfunction "A_2") (pintype "passive"))
      (node (ref "R1") (pin "1") (pinfunction "1_1") (pintype "passive"))
    )
    (net (code "37") (name "Net-(LED2-A)") (class "Default")
      (node (ref "LED2") (pin "2") (pinfunction "A_2") (pintype "passive"))
      (node (ref "R3") (pin "1") (pinfunction "1_1") (pintype "passive"))
    )
    (net (code "38") (name "Net-(LED3-B)") (class "Default")
      (node (ref "LED3") (pin "4") (pinfunction "B_4") (pintype "passive"))
      (node (ref "R11") (pin "2") (pinfunction "2_2") (pintype "passive"))
    )
    (net (code "39") (name "Net-(LED3-G)") (class "Default")
      (node (ref "LED3") (pin "3") (pinfunction "G_3") (pintype "passive"))
      (node (ref "R10") (pin "2") (pinfunction "2_2") (pintype "passive"))
    )
    (net (code "40") (name "Net-(LED3-R)") (class "Default")
      (node (ref "LED3") (pin "2") (pinfunction "R_2") (pintype "passive"))
      (node (ref "R8") (pin "2") (pinfunction "2_2") (pintype "passive"))
    )
    (net (code "41") (name "Net-(LED4-A)") (class "Default")
      (node (ref "LED4") (pin "2") (pinfunction "A_2") (pintype "passive"))
      (node (ref "R9") (pin "1") (pinfunction "1_1") (pintype "passive"))
    )
    (net (code "42") (name "Net-(LED5-A)") (class "Default")
      (node (ref "LED5") (pin "2") (pinfunction "A_2") (pintype "passive"))
      (node (ref "R12") (pin "1") (pinfunction "1_1") (pintype "passive"))
    )
    (net (code "43") (name "Net-(LED6-B)") (class "Default")
      (node (ref "LED6") (pin "4") (pinfunction "B_4") (pintype "passive"))
      (node (ref "R18") (pin "2") (pinfunction "2_2") (pintype "passive"))
    )
    (net (code "44") (name "Net-(LED6-G)") (class "Default")
      (node (ref "LED6") (pin "3") (pinfunction "G_3") (pintype "passive"))
      (node (ref "R14") (pin "2") (pinfunction "2_2") (pintype "passive"))
    )
    (net (code "45") (name "Net-(LED6-R)") (class "Default")
      (node (ref "LED6") (pin "2") (pinfunction "R_2") (pintype "passive"))
      (node (ref "R13") (pin "2") (pinfunction "2_2") (pintype "passive"))
    )
    (net (code "46") (name "Net-(LED7-A)") (class "Default")
      (node (ref "LED7") (pin "2") (pinfunction "A_2") (pintype "passive"))
      (node (ref "R21") (pin "2") (pinfunction "2_2") (pintype "passive"))
    )
    (net (code "47") (name "Net-(LED7-K)") (class "Default")
      (node (ref "LED7") (pin "1") (pinfunction "K_1") (pintype "passive"))
      (node (ref "U2") (pin "7") (pinfunction "~{CHRG}_7") (pintype "passive"))
    )
    (net (code "48") (name "Net-(R23-Pad1)") (class "Default")
      (node (ref "R23") (pin "1") (pinfunction "1_1") (pintype "passive"))
      (node (ref "R24") (pin "2") (pinfunction "2_2") (pintype "passive"))
    )
    (net (code "49") (name "Net-(U1-VBAT)") (class "Default")
      (node (ref "R25") (pin "2") (pinfunction "2_2") (pintype "passive"))
      (node (ref "U1") (pin "40") (pinfunction "VBAT_40") (pintype "passive"))
    )
    (net (code "50") (name "Net-(U2-PROG)") (class "Default")
      (node (ref "R20") (pin "2") (pinfunction "2_2") (pintype "passive"))
      (node (ref "U2") (pin "2") (pinfunction "PROG_2") (pintype "passive"))
    )
    (net (code "51") (name "Net-(U3-FB)") (class "Default")
      (node (ref "R22") (pin "1") (pinfunction "1_1") (pintype "passive"))
      (node (ref "R23") (pin "2") (pinfunction "2_2") (pintype "passive"))
      (node (ref "U3") (pin "3") (pinfunction "FB_3") (pintype "passive"))
    )
    (net (code "52") (name "unconnected-(*-BL-Pad8)") (class "Default")
      (node (ref "*") (pin "8") (pinfunction "BL_8") (pintype "passive"))
    )
    (net (code "53") (name "unconnected-(J-D+-Pad3)") (class "Default")
      (node (ref "J") (pin "3") (pinfunction "D+_3") (pintype "passive"))
    )
    (net (code "54") (name "unconnected-(J-D--Pad2)") (class "Default")
      (node (ref "J") (pin "2") (pinfunction "D-_2") (pintype "passive"))
    )
    (net (code "55") (name "unconnected-(J2-COM-Pad9)") (class "Default")
      (node (ref "J2") (pin "9") (pinfunction "COM_9") (pintype "passive"))
    )
    (net (code "56") (name "unconnected-(J2-DAT1-Pad8)") (class "Default")
      (node (ref "J2") (pin "8") (pinfunction "DAT1_8") (pintype "passive"))
    )
    (net (code "57") (name "unconnected-(J2-DAT2-Pad1)") (class "Default")
      (node (ref "J2") (pin "1") (pinfunction "DAT2_1") (pintype "passive"))
    )
    (net (code "58") (name "unconnected-(J2-Pad10)") (class "Default")
      (node (ref "J2") (pin "10") (pinfunction "10_10") (pintype "passive"))
    )
    (net (code "59") (name "unconnected-(J2-Pad11)") (class "Default")
      (node (ref "J2") (pin "11") (pinfunction "11_11") (pintype "passive"))
    )
    (net (code "60") (name "unconnected-(J2-Pad12)") (class "Default")
      (node (ref "J2") (pin "12") (pinfunction "12_12") (pintype "passive"))
    )
    (net (code "61") (name "unconnected-(J2-Pad13)") (class "Default")
      (node (ref "J2") (pin "13") (pinfunction "13_13") (pintype "passive"))
    )
    (net (code "62") (name "unconnected-(J2-PadCD1)") (class "Default")
      (node (ref "J2") (pin "CD1") (pinfunction "CD1_CD1") (pintype "passive"))
    )
    (net (code "63") (name "unconnected-(U1-A8-Pad5)") (class "Default")
      (node (ref "U1") (pin "5") (pinfunction "A8_5") (pintype "passive"))
    )
    (net (code "64") (name "unconnected-(U1-A9-Pad6)") (class "Default")
      (node (ref "U1") (pin "6") (pinfunction "A9_6") (pintype "passive"))
    )
    (net (code "65") (name "unconnected-(U1-A10-Pad7)") (class "Default")
      (node (ref "U1") (pin "7") (pinfunction "A10_7") (pintype "passive"))
    )
    (net (code "66") (name "unconnected-(U1-B8-Pad16)") (class "Default")
      (node (ref "U1") (pin "16") (pinfunction "B8_16") (pintype "passive"))
    )
    (net (code "67") (name "unconnected-(U1-B9-Pad17)") (class "Default")
      (node (ref "U1") (pin "17") (pinfunction "B9_17") (pintype "passive"))
    )
    (net (code "68") (name "unconnected-(U1-C14-Pad38)") (class "Default")
      (node (ref "U1") (pin "38") (pinfunction "C14_38") (pintype "passive"))
    )
    (net (code "69") (name "unconnected-(U1-C15-Pad37)") (class "Default")
      (node (ref "U1") (pin "37") (pinfunction "C15_37") (pintype "passive"))
    )
    (net (code "70") (name "unconnected-(U2-~{STDBY}-Pad6)") (class "Default")
      (node (ref "U2") (pin "6") (pinfunction "~{STDBY}_6") (pintype "passive"))
    )
    (net (code "71") (name "unconnected-(U3-NC-Pad6)") (class "Default")
      (node (ref "U3") (pin "6") (pinfunction "NC_6") (pintype "passive"))
    )
  )
)
